# DC_Power.net
KiCad netlist of a schematic drawn in EAGLE
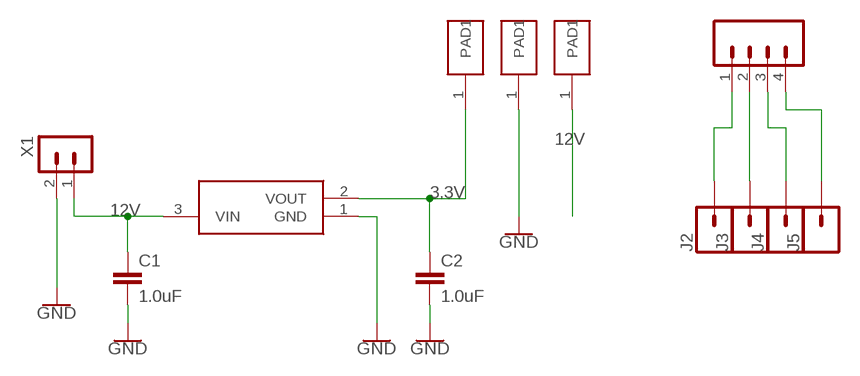
[diagram p0: schematic, sheet 1]

(export (version "E")
  (design (tool "Eeschema 10.0.6"))
  (components
    (comp (ref "C1")
      (value "1.0uF")
      (footprint "eagle-import:0805")
      (libsource (lib "eagle-import") (part "1.0UF-0805-25V-10%"))
    )
    (comp (ref "C2")
      (value "1.0uF")
      (footprint "eagle-import:0805")
      (libsource (lib "eagle-import") (part "1.0UF-0805-25V-10%"))
    )
    (comp (ref "IC1")
      (value "MCP1700T-3302E_TT")
      (footprint "eagle-import:SOT95P237X112-3N")
      (fields
        (field (name "MANUFACTURER_PART_NUMBER") "MCP1700T-3302E/TT")
        (field (name "MOUSER_PART_NUMBER") "579-MCP1700T3302E/TT")
      )
      (libsource (lib "eagle-import") (part "MCP1700T-3302E_TT"))
    )
    (comp (ref "J1")
      (value "CONN_041.27MM")
      (footprint "eagle-import:1X04_1.27MM")
      (libsource (lib "eagle-import") (part "CONN_041.27MM"))
    )
    (comp (ref "J2")
      (value "CONN_01PTH_NO_SILK_YES_STOP")
      (footprint "eagle-import:1X01_NO_SILK")
      (libsource (lib "eagle-import") (part "CONN_01PTH_NO_SILK_YES_STOP"))
    )
    (comp (ref "J3")
      (value "CONN_01PTH_NO_SILK_YES_STOP")
      (footprint "eagle-import:1X01_NO_SILK")
      (libsource (lib "eagle-import") (part "CONN_01PTH_NO_SILK_YES_STOP"))
    )
    (comp (ref "J4")
      (value "CONN_01PTH_NO_SILK_YES_STOP")
      (footprint "eagle-import:1X01_NO_SILK")
      (libsource (lib "eagle-import") (part "CONN_01PTH_NO_SILK_YES_STOP"))
    )
    (comp (ref "J5")
      (value "CONN_01PTH_NO_SILK_YES_STOP")
      (footprint "eagle-import:1X01_NO_SILK")
      (libsource (lib "eagle-import") (part "CONN_01PTH_NO_SILK_YES_STOP"))
    )
    (comp (ref "U$1")
      (value "SINGLE_1.27MM_HOLE")
      (footprint "eagle-import:1.27MM_SINGLE_HOLE")
      (libsource (lib "eagle-import") (part "SINGLE_1.27MM_HOLE"))
    )
    (comp (ref "U$2")
      (value "SINGLE_1.27MM_HOLE")
      (footprint "eagle-import:1.27MM_SINGLE_HOLE")
      (libsource (lib "eagle-import") (part "SINGLE_1.27MM_HOLE"))
    )
    (comp (ref "U$3")
      (value "SINGLE_1.27MM_HOLE")
      (footprint "eagle-import:1.27MM_SINGLE_HOLE")
      (libsource (lib "eagle-import") (part "SINGLE_1.27MM_HOLE"))
    )
    (comp (ref "X1")
      (value "BM02B-SRSS-TB")
      (footprint "eagle-import:BM02B-SRSS-TB")
      (libsource (lib "eagle-import") (part "BM02B-SRSS-TB"))
    )
  )
  (nets
    (net (code "1") (name "/3.3V") (class "Default")
      (node (ref "C2") (pin "1") (pinfunction "1_1") (pintype "passive"))
      (node (ref "IC1") (pin "2") (pinfunction "VOUT_2") (pintype "bidirectional"))
      (node (ref "U$1") (pin "1") (pinfunction "PAD1_1") (pintype "bidirectional"))
    )
    (net (code "2") (name "/12V") (class "Default")
      (node (ref "C1") (pin "1") (pinfunction "1_1") (pintype "passive"))
      (node (ref "IC1") (pin "3") (pinfunction "VIN_3") (pintype "bidirectional"))
      (node (ref "U$3") (pin "1") (pinfunction "PAD1_1") (pintype "bidirectional"))
      (node (ref "X1") (pin "1") (pinfunction "1_1") (pintype "passive"))
    )
    (net (code "3") (name "GND") (class "Default")
      (node (ref "C1") (pin "2") (pinfunction "2_2") (pintype "passive"))
      (node (ref "C2") (pin "2") (pinfunction "2_2") (pintype "passive"))
      (node (ref "IC1") (pin "1") (pinfunction "GND_1") (pintype "bidirectional"))
      (node (ref "U$2") (pin "1") (pinfunction "PAD1_1") (pintype "bidirectional"))
      (node (ref "X1") (pin "2") (pinfunction "2_2") (pintype "passive"))
    )
    (net (code "4") (name "Net-(J1-Pad1)") (class "Default")
      (node (ref "J1") (pin "1") (pinfunction "1_1") (pintype "passive"))
      (node (ref "J2") (pin "1") (pinfunction "1_1") (pintype "passive"))
    )
    (net (code "5") (name "Net-(J1-Pad2)") (class "Default")
      (node (ref "J1") (pin "2") (pinfunction "2_2") (pintype "passive"))
      (node (ref "J3") (pin "1") (pinfunction "1_1") (pintype "passive"))
    )
    (net (code "6") (name "Net-(J1-Pad3)") (class "Default")
      (node (ref "J1") (pin "3") (pinfunction "3_3") (pintype "passive"))
      (node (ref "J4") (pin "1") (pinfunction "1_1") (pintype "passive"))
    )
    (net (code "7") (name "Net-(J1-Pad4)") (class "Default")
      (node (ref "J1") (pin "4") (pinfunction "4_4") (pintype "passive"))
      (node (ref "J5") (pin "1") (pinfunction "1_1") (pintype "passive"))
    )
  )
)
